# clockBot_userInterface.net
KiCad netlist of a schematic drawn in EAGLE
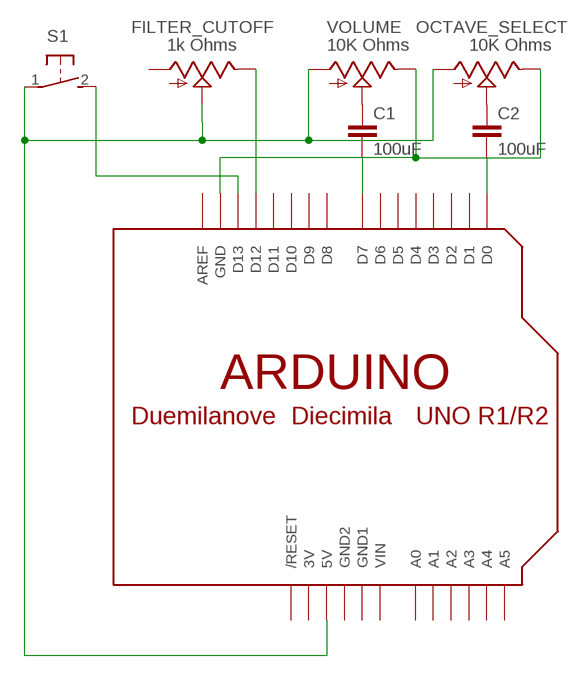
[diagram p0: schematic, sheet 1]

(export (version "E")
  (design (tool "Eeschema 10.0.6"))
  (components
    (comp (ref "C1")
      (value "100uF")
      (footprint "eagle-import:C5B2.5")
      (libsource (lib "eagle-import") (part "C5/2.5"))
    )
    (comp (ref "C2")
      (value "100uF")
      (footprint "eagle-import:C5B2.5")
      (libsource (lib "eagle-import") (part "C5/2.5"))
    )
    (comp (ref "FILTER_CUTOFF")
      (value "1k Ohms")
      (footprint "eagle-import:S64W")
      (libsource (lib "eagle-import") (part "TRIM_US-S64W"))
    )
    (comp (ref "OCTAVE_SELECT")
      (value "10K Ohms")
      (footprint "eagle-import:S64W")
      (libsource (lib "eagle-import") (part "TRIM_US-S64W"))
    )
    (comp (ref "S1")
      (value "31-XX")
      (footprint "eagle-import:B3F-31XX")
      (libsource (lib "eagle-import") (part "31-XX"))
    )
    (comp (ref "U$1")
      (value "ARDUINO-NODIM")
      (footprint "eagle-import:ARDUINO-NODIM")
      (libsource (lib "eagle-import") (part "ARDUINO-NODIM"))
    )
    (comp (ref "VOLUME")
      (value "10K Ohms")
      (footprint "eagle-import:S64W")
      (libsource (lib "eagle-import") (part "TRIM_US-S64W"))
    )
  )
  (nets
    (net (code "1") (name "/3V") (class "Default")
      (node (ref "U$1") (pin "3V") (pinfunction "3V_3V") (pintype "power_in"))
    )
    (net (code "2") (name "/GND1") (class "Default")
      (node (ref "U$1") (pin "GND1") (pinfunction "GND1_GND1") (pintype "power_in"))
    )
    (net (code "3") (name "/GND2") (class "Default")
      (node (ref "U$1") (pin "GND2") (pinfunction "GND2_GND2") (pintype "power_in"))
    )
    (net (code "4") (name "/VIN") (class "Default")
      (node (ref "U$1") (pin "VIN") (pinfunction "VIN_VIN") (pintype "power_in"))
    )
    (net (code "5") (name "Net-(C1-Pad1)") (class "Default")
      (node (ref "C1") (pin "1") (pinfunction "1_1") (pintype "passive"))
      (node (ref "VOLUME") (pin "S") (pinfunction "S_S") (pintype "passive"))
    )
    (net (code "6") (name "Net-(C1-Pad2)") (class "Default")
      (node (ref "C1") (pin "2") (pinfunction "2_2") (pintype "passive"))
      (node (ref "U$1") (pin "D7") (pinfunction "D7_D7") (pintype "bidirectional"))
    )
    (net (code "7") (name "Net-(C2-Pad1)") (class "Default")
      (node (ref "C2") (pin "1") (pinfunction "1_1") (pintype "passive"))
      (node (ref "OCTAVE_SELECT") (pin "S") (pinfunction "S_S") (pintype "passive"))
    )
    (net (code "8") (name "Net-(C2-Pad2)") (class "Default")
      (node (ref "C2") (pin "2") (pinfunction "2_2") (pintype "passive"))
      (node (ref "U$1") (pin "D0") (pinfunction "D0_D0") (pintype "bidirectional"))
    )
    (net (code "9") (name "Net-(FILTER_CUTOFF-PadE)") (class "Default")
      (node (ref "FILTER_CUTOFF") (pin "E") (pinfunction "E_E") (pintype "passive"))
      (node (ref "U$1") (pin "D12") (pinfunction "D12_D12") (pintype "bidirectional"))
    )
    (net (code "10") (name "Net-(OCTAVE_SELECT-PadE)") (class "Default")
      (node (ref "OCTAVE_SELECT") (pin "E") (pinfunction "E_E") (pintype "passive"))
      (node (ref "U$1") (pin "GND") (pinfunction "GND_GND") (pintype "power_in"))
      (node (ref "VOLUME") (pin "E") (pinfunction "E_E") (pintype "passive"))
    )
    (net (code "11") (name "Net-(S1-P)") (class "Default")
      (node (ref "FILTER_CUTOFF") (pin "S") (pinfunction "S_S") (pintype "passive"))
      (node (ref "OCTAVE_SELECT") (pin "A") (pinfunction "A_A") (pintype "passive"))
      (node (ref "S1") (pin "1") (pinfunction "P_1") (pintype "passive"))
      (node (ref "U$1") (pin "5V") (pinfunction "5V_5V") (pintype "power_in"))
      (node (ref "VOLUME") (pin "A") (pinfunction "A_A") (pintype "passive"))
    )
    (net (code "12") (name "Net-(S1-S)") (class "Default")
      (node (ref "S1") (pin "2") (pinfunction "S_2") (pintype "passive"))
      (node (ref "U$1") (pin "D13") (pinfunction "D13_D13") (pintype "bidirectional"))
    )
    (net (code "13") (name "unconnected-(FILTER_CUTOFF-PadA)") (class "Default")
      (node (ref "FILTER_CUTOFF") (pin "A") (pinfunction "A_A") (pintype "passive"))
    )
    (net (code "14") (name "unconnected-(U$1-PadA0)") (class "Default")
      (node (ref "U$1") (pin "A0") (pinfunction "A0_A0") (pintype "bidirectional"))
    )
    (net (code "15") (name "unconnected-(U$1-PadA1)") (class "Default")
      (node (ref "U$1") (pin "A1") (pinfunction "A1_A1") (pintype "bidirectional"))
    )
    (net (code "16") (name "unconnected-(U$1-PadA2)") (class "Default")
      (node (ref "U$1") (pin "A2") (pinfunction "A2_A2") (pintype "bidirectional"))
    )
    (net (code "17") (name "unconnected-(U$1-PadA3)") (class "Default")
      (node (ref "U$1") (pin "A3") (pinfunction "A3_A3") (pintype "bidirectional"))
    )
    (net (code "18") (name "unconnected-(U$1-PadA4)") (class "Default")
      (node (ref "U$1") (pin "A4") (pinfunction "A4_A4") (pintype "bidirectional"))
    )
    (net (code "19") (name "unconnected-(U$1-PadA5)") (class "Default")
      (node (ref "U$1") (pin "A5") (pinfunction "A5_A5") (pintype "bidirectional"))
    )
    (net (code "20") (name "unconnected-(U$1-PadAREF)") (class "Default")
      (node (ref "U$1") (pin "AREF") (pinfunction "AREF_AREF") (pintype "bidirectional"))
    )
    (net (code "21") (name "unconnected-(U$1-PadD1)") (class "Default")
      (node (ref "U$1") (pin "D1") (pinfunction "D1_D1") (pintype "bidirectional"))
    )
    (net (code "22") (name "unconnected-(U$1-PadD2)") (class "Default")
      (node (ref "U$1") (pin "D2") (pinfunction "D2_D2") (pintype "bidirectional"))
    )
    (net (code "23") (name "unconnected-(U$1-PadD3)") (class "Default")
      (node (ref "U$1") (pin "D3") (pinfunction "D3_D3") (pintype "bidirectional"))
    )
    (net (code "24") (name "unconnected-(U$1-PadD4)") (class "Default")
      (node (ref "U$1") (pin "D4") (pinfunction "D4_D4") (pintype "bidirectional"))
    )
    (net (code "25") (name "unconnected-(U$1-PadD5)") (class "Default")
      (node (ref "U$1") (pin "D5") (pinfunction "D5_D5") (pintype "bidirectional"))
    )
    (net (code "26") (name "unconnected-(U$1-PadD6)") (class "Default")
      (node (ref "U$1") (pin "D6") (pinfunction "D6_D6") (pintype "bidirectional"))
    )
    (net (code "27") (name "unconnected-(U$1-PadD8)") (class "Default")
      (node (ref "U$1") (pin "D8") (pinfunction "D8_D8") (pintype "bidirectional"))
    )
    (net (code "28") (name "unconnected-(U$1-PadD9)") (class "Default")
      (node (ref "U$1") (pin "D9") (pinfunction "D9_D9") (pintype "bidirectional"))
    )
    (net (code "29") (name "unconnected-(U$1-PadD10)") (class "Default")
      (node (ref "U$1") (pin "D10") (pinfunction "D10_D10") (pintype "bidirectional"))
    )
    (net (code "30") (name "unconnected-(U$1-PadD11)") (class "Default")
      (node (ref "U$1") (pin "D11") (pinfunction "D11_D11") (pintype "bidirectional"))
    )
    (net (code "31") (name "unconnected-(U$1-{slash}RESET-PadRESET)") (class "Default")
      (node (ref "U$1") (pin "RESET") (pinfunction "/RESET_RESET") (pintype "bidirectional"))
    )
  )
)
